# OnlyRes.net
KiCad netlist of a schematic drawn in Altium Designer
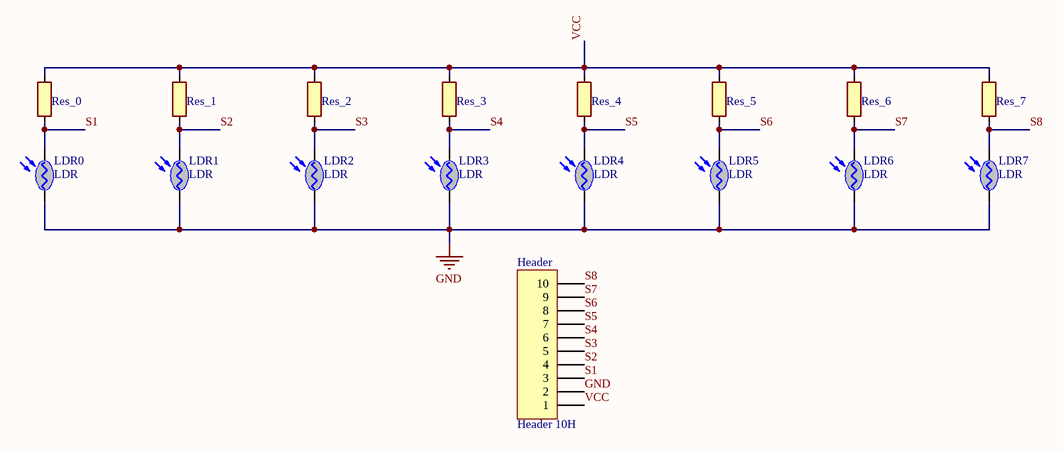
[diagram p0: OnlyRes.SchDoc]

(export (version "E")
  (design (tool "Eeschema 10.0.6"))
  (components
    (comp (ref "Header")
      (value "Header 10H")
      (footprint "HDR1X10H")
      (description "Header, 10-Pin, Right Angle")
      (fields (field (name "PUBLISHER") "Altium Limited"))
      (libsource (lib "Miscellaneous Connectors") (part "Header 10H"))
    )
    (comp (ref "LDR0")
      (value "LDR")
      (footprint "CDS")
      (description "Quang Tro")
      (libsource (lib "LIBRARY") (part "LDR"))
    )
    (comp (ref "LDR1")
      (value "LDR")
      (footprint "CDS")
      (description "Quang Tro")
      (libsource (lib "LIBRARY") (part "LDR"))
    )
    (comp (ref "LDR2")
      (value "LDR")
      (footprint "CDS")
      (description "Quang Tro")
      (libsource (lib "LIBRARY") (part "LDR"))
    )
    (comp (ref "LDR3")
      (value "LDR")
      (footprint "CDS")
      (description "Quang Tro")
      (libsource (lib "LIBRARY") (part "LDR"))
    )
    (comp (ref "LDR4")
      (value "LDR")
      (footprint "CDS")
      (description "Quang Tro")
      (libsource (lib "LIBRARY") (part "LDR"))
    )
    (comp (ref "LDR5")
      (value "LDR")
      (footprint "CDS")
      (description "Quang Tro")
      (libsource (lib "LIBRARY") (part "LDR"))
    )
    (comp (ref "LDR6")
      (value "LDR")
      (footprint "CDS")
      (description "Quang Tro")
      (libsource (lib "LIBRARY") (part "LDR"))
    )
    (comp (ref "LDR7")
      (value "LDR")
      (footprint "CDS")
      (description "Quang Tro")
      (libsource (lib "LIBRARY") (part "LDR"))
    )
    (comp (ref "Res_0")
      (value "Res")
      (footprint "Resistor_300mil")
      (libsource (lib "Duongw_lib") (part "Res"))
    )
    (comp (ref "Res_1") (value "Res") (footprint "Resistor_300mil") (libsource (lib "") (part "Res_1")))
    (comp (ref "Res_2")
      (value "Res")
      (footprint "Resistor_300mil")
      (libsource (lib "Duongw_lib") (part "Res"))
    )
    (comp (ref "Res_3")
      (value "Res")
      (footprint "Resistor_300mil")
      (libsource (lib "Duongw_lib") (part "Res"))
    )
    (comp (ref "Res_4")
      (value "Res")
      (footprint "Resistor_300mil")
      (libsource (lib "Duongw_lib") (part "Res"))
    )
    (comp (ref "Res_5")
      (value "Res")
      (footprint "Resistor_300mil")
      (libsource (lib "Duongw_lib") (part "Res"))
    )
    (comp (ref "Res_6") (value "Res") (footprint "Resistor_300mil") (libsource (lib "") (part "Res_1")))
    (comp (ref "Res_7")
      (value "Res")
      (footprint "Resistor_300mil")
      (libsource (lib "Duongw_lib") (part "Res"))
    )
  )
  (nets
    (net (code "1") (name "/S1") (class "Default")
      (node (ref "Header") (pin "3") (pinfunction "3_3") (pintype "passive"))
      (node (ref "LDR0") (pin "2") (pinfunction "K_2") (pintype "passive"))
      (node (ref "Res_0") (pin "1") (pinfunction "1_1") (pintype "passive"))
    )
    (net (code "2") (name "/S2") (class "Default")
      (node (ref "Header") (pin "4") (pinfunction "4_4") (pintype "passive"))
      (node (ref "LDR1") (pin "2") (pinfunction "K_2") (pintype "passive"))
      (node (ref "Res_1") (pin "2") (pinfunction "2_2") (pintype "passive"))
    )
    (net (code "3") (name "/S3") (class "Default")
      (node (ref "Header") (pin "5") (pinfunction "5_5") (pintype "passive"))
      (node (ref "LDR2") (pin "2") (pinfunction "K_2") (pintype "passive"))
      (node (ref "Res_2") (pin "1") (pinfunction "1_1") (pintype "passive"))
    )
    (net (code "4") (name "/S4") (class "Default")
      (node (ref "Header") (pin "6") (pinfunction "6_6") (pintype "passive"))
      (node (ref "LDR3") (pin "2") (pinfunction "K_2") (pintype "passive"))
      (node (ref "Res_3") (pin "1") (pinfunction "1_1") (pintype "passive"))
    )
    (net (code "5") (name "/S5") (class "Default")
      (node (ref "Header") (pin "7") (pinfunction "7_7") (pintype "passive"))
      (node (ref "LDR4") (pin "2") (pinfunction "K_2") (pintype "passive"))
      (node (ref "Res_4") (pin "1") (pinfunction "1_1") (pintype "passive"))
    )
    (net (code "6") (name "/S6") (class "Default")
      (node (ref "Header") (pin "8") (pinfunction "8_8") (pintype "passive"))
      (node (ref "LDR5") (pin "2") (pinfunction "K_2") (pintype "passive"))
      (node (ref "Res_5") (pin "1") (pinfunction "1_1") (pintype "passive"))
    )
    (net (code "7") (name "/S7") (class "Default")
      (node (ref "Header") (pin "9") (pinfunction "9_9") (pintype "passive"))
      (node (ref "LDR6") (pin "2") (pinfunction "K_2") (pintype "passive"))
      (node (ref "Res_6") (pin "2") (pinfunction "2_2") (pintype "passive"))
    )
    (net (code "8") (name "/S8") (class "Default")
      (node (ref "Header") (pin "10") (pinfunction "10_10") (pintype "passive"))
      (node (ref "LDR7") (pin "2") (pinfunction "K_2") (pintype "passive"))
      (node (ref "Res_7") (pin "1") (pinfunction "1_1") (pintype "passive"))
    )
    (net (code "9") (name "/VCC") (class "Default")
      (node (ref "Header") (pin "1") (pinfunction "1_1") (pintype "passive"))
      (node (ref "Res_0") (pin "2") (pinfunction "2_2") (pintype "passive"))
      (node (ref "Res_1") (pin "1") (pinfunction "1_1") (pintype "passive"))
      (node (ref "Res_2") (pin "2") (pinfunction "2_2") (pintype "passive"))
      (node (ref "Res_3") (pin "2") (pinfunction "2_2") (pintype "passive"))
      (node (ref "Res_4") (pin "2") (pinfunction "2_2") (pintype "passive"))
      (node (ref "Res_5") (pin "2") (pinfunction "2_2") (pintype "passive"))
      (node (ref "Res_6") (pin "1") (pinfunction "1_1") (pintype "passive"))
      (node (ref "Res_7") (pin "2") (pinfunction "2_2") (pintype "passive"))
    )
    (net (code "10") (name "GND") (class "Default")
      (node (ref "Header") (pin "2") (pinfunction "2_2") (pintype "passive"))
      (node (ref "LDR0") (pin "1") (pinfunction "A_1") (pintype "passive"))
      (node (ref "LDR1") (pin "1") (pinfunction "A_1") (pintype "passive"))
      (node (ref "LDR2") (pin "1") (pinfunction "A_1") (pintype "passive"))
      (node (ref "LDR3") (pin "1") (pinfunction "A_1") (pintype "passive"))
      (node (ref "LDR4") (pin "1") (pinfunction "A_1") (pintype "passive"))
      (node (ref "LDR5") (pin "1") (pinfunction "A_1") (pintype "passive"))
      (node (ref "LDR6") (pin "1") (pinfunction "A_1") (pintype "passive"))
      (node (ref "LDR7") (pin "1") (pinfunction "A_1") (pintype "passive"))
    )
  )
)
